# IO_Connector.net
KiCad netlist of a schematic drawn in Altium Designer
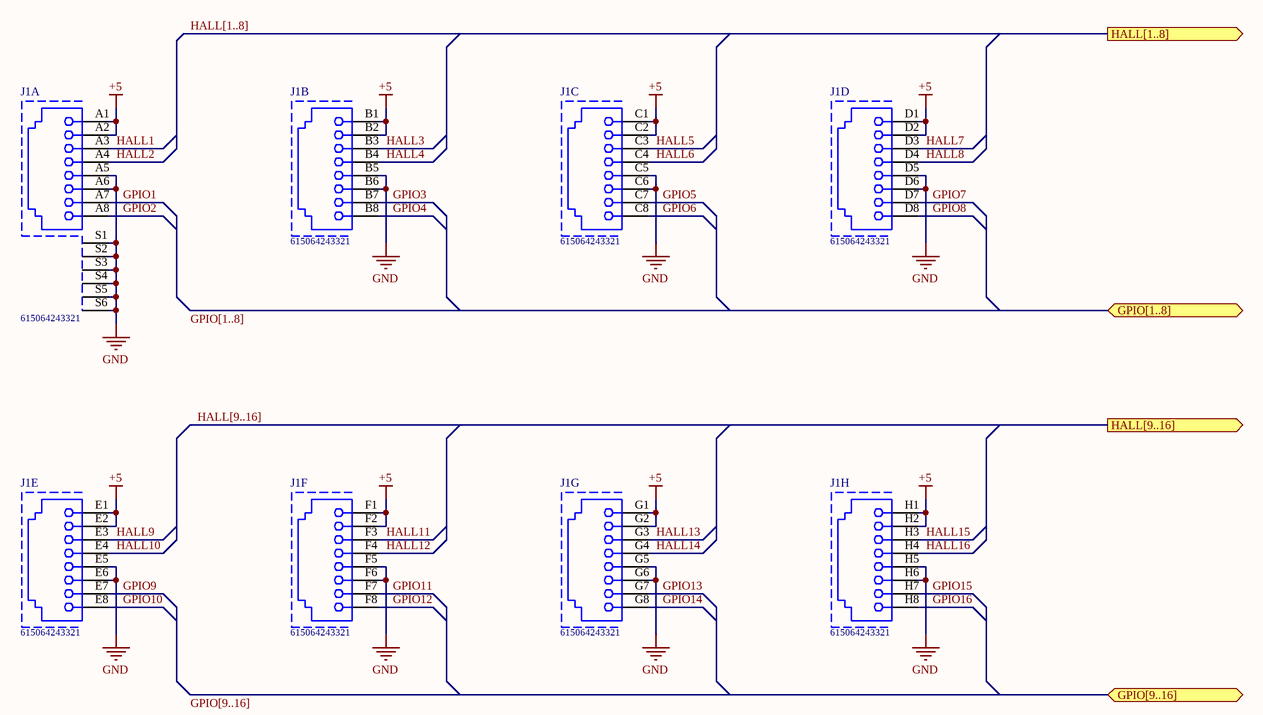
[diagram p0: IO_Connector.SchDoc]

(export (version "E")
  (design (tool "Eeschema 10.0.6"))
  (components
    (comp (ref "J1")
      (value "615064243321")
      (footprint "615064243321")
      (fields (field (name "MANUFACTURER") "Wurth Elektronik") (field (name "PUBLISHER") "WurthElektronik"))
      (libsource (lib "Altium Content Vault") (part "WE-CN-8P-6F-J64"))
    )
  )
  (nets
    (net (code "1") (name "+5") (class "Default")
      (node (ref "J1") (pin "A1") (pinfunction "A1_A1") (pintype "passive"))
      (node (ref "J1") (pin "A2") (pinfunction "A2_A2") (pintype "passive"))
      (node (ref "J1") (pin "B1") (pinfunction "B1_B1") (pintype "passive"))
      (node (ref "J1") (pin "B2") (pinfunction "B2_B2") (pintype "passive"))
      (node (ref "J1") (pin "C1") (pinfunction "C1_C1") (pintype "passive"))
      (node (ref "J1") (pin "C2") (pinfunction "C2_C2") (pintype "passive"))
      (node (ref "J1") (pin "D1") (pinfunction "D1_D1") (pintype "passive"))
      (node (ref "J1") (pin "D2") (pinfunction "D2_D2") (pintype "passive"))
      (node (ref "J1") (pin "E1") (pinfunction "E1_E1") (pintype "passive"))
      (node (ref "J1") (pin "E2") (pinfunction "E2_E2") (pintype "passive"))
      (node (ref "J1") (pin "F1") (pinfunction "F1_F1") (pintype "passive"))
      (node (ref "J1") (pin "F2") (pinfunction "F2_F2") (pintype "passive"))
      (node (ref "J1") (pin "G1") (pinfunction "G1_G1") (pintype "passive"))
      (node (ref "J1") (pin "G2") (pinfunction "G2_G2") (pintype "passive"))
      (node (ref "J1") (pin "H1") (pinfunction "H1_H1") (pintype "passive"))
      (node (ref "J1") (pin "H2") (pinfunction "H2_H2") (pintype "passive"))
    )
    (net (code "2") (name "/GPIO1") (class "Default")
      (node (ref "J1") (pin "A7") (pinfunction "A7_A7") (pintype "passive"))
    )
    (net (code "3") (name "/GPIO2") (class "Default")
      (node (ref "J1") (pin "A8") (pinfunction "A8_A8") (pintype "passive"))
    )
    (net (code "4") (name "/GPIO3") (class "Default")
      (node (ref "J1") (pin "B7") (pinfunction "B7_B7") (pintype "passive"))
    )
    (net (code "5") (name "/GPIO4") (class "Default")
      (node (ref "J1") (pin "B8") (pinfunction "B8_B8") (pintype "passive"))
    )
    (net (code "6") (name "/GPIO5") (class "Default")
      (node (ref "J1") (pin "C7") (pinfunction "C7_C7") (pintype "passive"))
    )
    (net (code "7") (name "/GPIO6") (class "Default")
      (node (ref "J1") (pin "C8") (pinfunction "C8_C8") (pintype "passive"))
    )
    (net (code "8") (name "/GPIO7") (class "Default")
      (node (ref "J1") (pin "D7") (pinfunction "D7_D7") (pintype "passive"))
    )
    (net (code "9") (name "/GPIO8") (class "Default")
      (node (ref "J1") (pin "D8") (pinfunction "D8_D8") (pintype "passive"))
    )
    (net (code "10") (name "/GPIO9") (class "Default")
      (node (ref "J1") (pin "E7") (pinfunction "E7_E7") (pintype "passive"))
    )
    (net (code "11") (name "/GPIO10") (class "Default")
      (node (ref "J1") (pin "E8") (pinfunction "E8_E8") (pintype "passive"))
    )
    (net (code "12") (name "/GPIO11") (class "Default")
      (node (ref "J1") (pin "F7") (pinfunction "F7_F7") (pintype "passive"))
    )
    (net (code "13") (name "/GPIO12") (class "Default")
      (node (ref "J1") (pin "F8") (pinfunction "F8_F8") (pintype "passive"))
    )
    (net (code "14") (name "/GPIO13") (class "Default")
      (node (ref "J1") (pin "G7") (pinfunction "G7_G7") (pintype "passive"))
    )
    (net (code "15") (name "/GPIO14") (class "Default")
      (node (ref "J1") (pin "G8") (pinfunction "G8_G8") (pintype "passive"))
    )
    (net (code "16") (name "/GPIO15") (class "Default")
      (node (ref "J1") (pin "H7") (pinfunction "H7_H7") (pintype "passive"))
    )
    (net (code "17") (name "/GPIO16") (class "Default")
      (node (ref "J1") (pin "H8") (pinfunction "H8_H8") (pintype "passive"))
    )
    (net (code "20") (name "/HALL1") (class "Default")
      (node (ref "J1") (pin "A3") (pinfunction "A3_A3") (pintype "passive"))
    )
    (net (code "21") (name "/HALL2") (class "Default")
      (node (ref "J1") (pin "A4") (pinfunction "A4_A4") (pintype "passive"))
    )
    (net (code "22") (name "/HALL3") (class "Default")
      (node (ref "J1") (pin "B3") (pinfunction "B3_B3") (pintype "passive"))
    )
    (net (code "23") (name "/HALL4") (class "Default")
      (node (ref "J1") (pin "B4") (pinfunction "B4_B4") (pintype "passive"))
    )
    (net (code "24") (name "/HALL5") (class "Default")
      (node (ref "J1") (pin "C3") (pinfunction "C3_C3") (pintype "passive"))
    )
    (net (code "25") (name "/HALL6") (class "Default")
      (node (ref "J1") (pin "C4") (pinfunction "C4_C4") (pintype "passive"))
    )
    (net (code "26") (name "/HALL7") (class "Default")
      (node (ref "J1") (pin "D3") (pinfunction "D3_D3") (pintype "passive"))
    )
    (net (code "27") (name "/HALL8") (class "Default")
      (node (ref "J1") (pin "D4") (pinfunction "D4_D4") (pintype "passive"))
    )
    (net (code "28") (name "/HALL9") (class "Default")
      (node (ref "J1") (pin "E3") (pinfunction "E3_E3") (pintype "passive"))
    )
    (net (code "29") (name "/HALL10") (class "Default")
      (node (ref "J1") (pin "E4") (pinfunction "E4_E4") (pintype "passive"))
    )
    (net (code "30") (name "/HALL11") (class "Default")
      (node (ref "J1") (pin "F3") (pinfunction "F3_F3") (pintype "passive"))
    )
    (net (code "31") (name "/HALL12") (class "Default")
      (node (ref "J1") (pin "F4") (pinfunction "F4_F4") (pintype "passive"))
    )
    (net (code "32") (name "/HALL13") (class "Default")
      (node (ref "J1") (pin "G3") (pinfunction "G3_G3") (pintype "passive"))
    )
    (net (code "33") (name "/HALL14") (class "Default")
      (node (ref "J1") (pin "G4") (pinfunction "G4_G4") (pintype "passive"))
    )
    (net (code "34") (name "/HALL15") (class "Default")
      (node (ref "J1") (pin "H3") (pinfunction "H3_H3") (pintype "passive"))
    )
    (net (code "35") (name "/HALL16") (class "Default")
      (node (ref "J1") (pin "H4") (pinfunction "H4_H4") (pintype "passive"))
    )
    (net (code "38") (name "GND") (class "Default")
      (node (ref "J1") (pin "A5") (pinfunction "A5_A5") (pintype "passive"))
      (node (ref "J1") (pin "A6") (pinfunction "A6_A6") (pintype "passive"))
      (node (ref "J1") (pin "B5") (pinfunction "B5_B5") (pintype "passive"))
      (node (ref "J1") (pin "B6") (pinfunction "B6_B6") (pintype "passive"))
      (node (ref "J1") (pin "C5") (pinfunction "C5_C5") (pintype "passive"))
      (node (ref "J1") (pin "C6") (pinfunction "C6_C6") (pintype "passive"))
      (node (ref "J1") (pin "D5") (pinfunction "D5_D5") (pintype "passive"))
      (node (ref "J1") (pin "D6") (pinfunction "D6_D6") (pintype "passive"))
      (node (ref "J1") (pin "E5") (pinfunction "E5_E5") (pintype "passive"))
      (node (ref "J1") (pin "E6") (pinfunction "E6_E6") (pintype "passive"))
      (node (ref "J1") (pin "F5") (pinfunction "F5_F5") (pintype "passive"))
      (node (ref "J1") (pin "F6") (pinfunction "F6_F6") (pintype "passive"))
      (node (ref "J1") (pin "G5") (pinfunction "G5_G5") (pintype "passive"))
      (node (ref "J1") (pin "G6") (pinfunction "G6_G6") (pintype "passive"))
      (node (ref "J1") (pin "H5") (pinfunction "H5_H5") (pintype "passive"))
      (node (ref "J1") (pin "H6") (pinfunction "H6_H6") (pintype "passive"))
      (node (ref "J1") (pin "S1") (pinfunction "S1_S1") (pintype "passive"))
      (node (ref "J1") (pin "S2") (pinfunction "S2_S2") (pintype "passive"))
      (node (ref "J1") (pin "S3") (pinfunction "S3_S3") (pintype "passive"))
      (node (ref "J1") (pin "S4") (pinfunction "S4_S4") (pintype "passive"))
      (node (ref "J1") (pin "S5") (pinfunction "S5_S5") (pintype "passive"))
      (node (ref "J1") (pin "S6") (pinfunction "S6_S6") (pintype "passive"))
    )
  )
)
